# AMSTOMQTT.net
KiCad netlist of a schematic drawn in Altium Designer
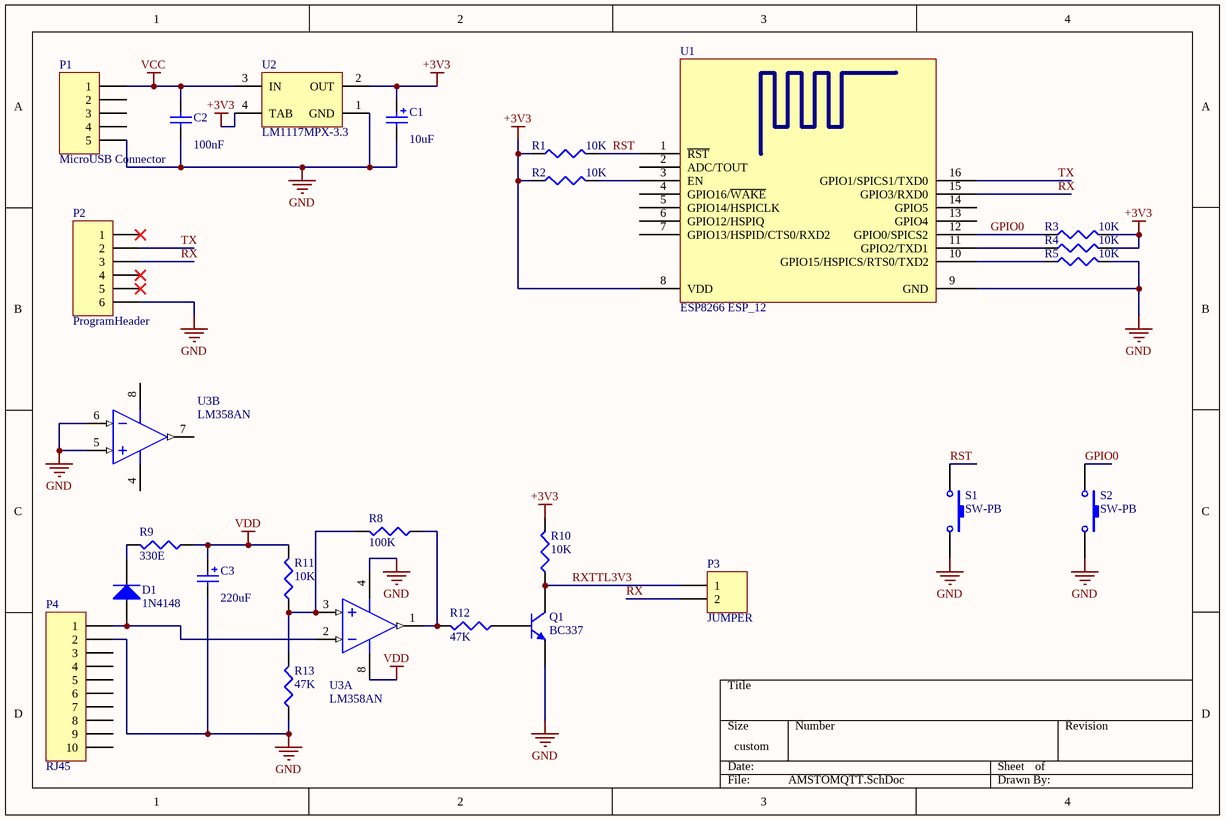
[diagram p0: AMSTOMQTT.SchDoc]

(export (version "E")
  (design (tool "Eeschema 10.0.6"))
  (components
    (comp (ref "C1")
      (value "10uF")
      (footprint "CAP(10uF/25V)")
      (description "Polarized Capacitor (Axial)")
      (fields (field (name "Comment") "Cap Pol2") (field (name "PUBLISHER") "Altium Limited"))
      (libsource (lib "Miscellaneous Devices") (part "Cap Pol2"))
    )
    (comp (ref "C2")
      (value "100nF")
      (footprint "RAD-0.2")
      (description "Capacitor")
      (fields (field (name "Comment") "Cap") (field (name "PUBLISHER") "Altium Limited"))
      (libsource (lib "Miscellaneous Devices") (part "Cap"))
    )
    (comp (ref "C3")
      (value "220uF")
      (footprint "CAP(10uF/25V)")
      (description "Polarized Capacitor (Axial)")
      (fields (field (name "Comment") "Cap Pol2") (field (name "PUBLISHER") "Altium Limited"))
      (libsource (lib "Miscellaneous Devices") (part "Cap Pol2"))
    )
    (comp (ref "D1")
      (value "1N4148")
      (footprint "DO-35")
      (description "High Conductance Fast Diode")
      (fields (field (name "PUBLISHER") "Altium Limited"))
      (libsource (lib "Miscellaneous Devices") (part "Diode 1N4148"))
    )
    (comp (ref "P1")
      (value "MicroUSB Connector")
      (footprint "MicroUSB")
      (description "Header, 5-Pin")
      (fields (field (name "PUBLISHER") "Altium Limited"))
      (libsource (lib "Miscellaneous Connectors") (part "Header 5"))
    )
    (comp (ref "P2")
      (value "ProgramHeader")
      (footprint "HDR1X6")
      (description "Header, 6-Pin")
      (fields (field (name "PUBLISHER") "Altium Limited"))
      (libsource (lib "Miscellaneous Connectors") (part "Header 6"))
    )
    (comp (ref "P3")
      (value "JUMPER")
      (footprint "HDR1X2")
      (description "Header, 2-Pin")
      (fields (field (name "PUBLISHER") "Altium Limited"))
      (libsource (lib "Miscellaneous Connectors") (part "Header 2"))
    )
    (comp (ref "P4")
      (value "RJ45")
      (footprint "RJ45")
      (description "Header, 10-Pin")
      (fields (field (name "PUBLISHER") "Altium Limited"))
      (libsource (lib "Miscellaneous Connectors") (part "Header 10"))
    )
    (comp (ref "Q1")
      (value "BC337")
      (footprint "TO-92")
      (description "NPN General Purpose Amplifier")
      (fields (field (name "PUBLISHER") "Altium Limited"))
      (libsource (lib "Miscellaneous Devices") (part "2N3904"))
    )
    (comp (ref "R1")
      (value "10K")
      (footprint "AXIAL-0.3")
      (description "Resistor")
      (fields (field (name "Comment") "Res3") (field (name "PUBLISHER") "Altium Limited"))
      (libsource (lib "Miscellaneous Devices") (part "Res3"))
    )
    (comp (ref "R2")
      (value "10K")
      (footprint "AXIAL-0.3")
      (description "Resistor")
      (fields (field (name "Comment") "Res3") (field (name "PUBLISHER") "Altium Limited"))
      (libsource (lib "Miscellaneous Devices") (part "Res3"))
    )
    (comp (ref "R3")
      (value "10K")
      (footprint "AXIAL-0.3")
      (description "Resistor")
      (fields (field (name "Comment") "Res3") (field (name "PUBLISHER") "Altium Limited"))
      (libsource (lib "Miscellaneous Devices") (part "Res3"))
    )
    (comp (ref "R4")
      (value "10K")
      (footprint "AXIAL-0.3")
      (description "Resistor")
      (fields (field (name "Comment") "Res3") (field (name "PUBLISHER") "Altium Limited"))
      (libsource (lib "Miscellaneous Devices") (part "Res3"))
    )
    (comp (ref "R5")
      (value "10K")
      (footprint "AXIAL-0.3")
      (description "Resistor")
      (fields (field (name "Comment") "Res3") (field (name "PUBLISHER") "Altium Limited"))
      (libsource (lib "Miscellaneous Devices") (part "Res3"))
    )
    (comp (ref "R8")
      (value "100K")
      (footprint "AXIAL-0.3")
      (description "Resistor")
      (fields (field (name "Comment") "Res3") (field (name "PUBLISHER") "Altium Limited"))
      (libsource (lib "Miscellaneous Devices") (part "Res3"))
    )
    (comp (ref "R9")
      (value "330E")
      (footprint "AXIAL-0.3")
      (description "Resistor")
      (fields (field (name "Comment") "Res3") (field (name "PUBLISHER") "Altium Limited"))
      (libsource (lib "Miscellaneous Devices") (part "Res3"))
    )
    (comp (ref "R10")
      (value "10K")
      (footprint "AXIAL-0.3")
      (description "Resistor")
      (fields (field (name "Comment") "Res3") (field (name "PUBLISHER") "Altium Limited"))
      (libsource (lib "Miscellaneous Devices") (part "Res3"))
    )
    (comp (ref "R11")
      (value "10K")
      (footprint "AXIAL-0.3")
      (description "Resistor")
      (fields (field (name "Comment") "Res3") (field (name "PUBLISHER") "Altium Limited"))
      (libsource (lib "Miscellaneous Devices") (part "Res3"))
    )
    (comp (ref "R12")
      (value "47K")
      (footprint "AXIAL-0.3")
      (description "Resistor")
      (fields (field (name "Comment") "Res3") (field (name "PUBLISHER") "Altium Limited"))
      (libsource (lib "Miscellaneous Devices") (part "Res3"))
    )
    (comp (ref "R13")
      (value "47K")
      (footprint "AXIAL-0.3")
      (description "Resistor")
      (fields (field (name "Comment") "Res3") (field (name "PUBLISHER") "Altium Limited"))
      (libsource (lib "Miscellaneous Devices") (part "Res3"))
    )
    (comp (ref "S1")
      (value "SW-PB")
      (footprint "PUSHBUTTON")
      (description "Switch")
      (fields (field (name "PUBLISHER") "Altium Limited"))
      (libsource (lib "Miscellaneous Devices") (part "SW-PB"))
    )
    (comp (ref "S2")
      (value "SW-PB")
      (footprint "PUSHBUTTON")
      (description "Switch")
      (fields (field (name "PUBLISHER") "Altium Limited"))
      (libsource (lib "Miscellaneous Devices") (part "SW-PB"))
    )
    (comp (ref "U1")
      (value "ESP8266 ESP_12")
      (footprint "ESP8266 ESP_12")
      (description "ESP8266 ESP-12")
      (fields (field (name "PUBLISHER") "Cynetik Group") (field (name "LATESTREVIEWER") "Zion Blue"))
      (libsource (lib "ESP8266") (part "ESP8266 ESP_12"))
    )
    (comp (ref "U2")
      (value "LM1117MPX-3.3")
      (footprint "MP04A_N")
      (description "800mA Low-Dropout Linear Regulator, 4-pin SOT-223")
      (fields (field (name "MANUFACTURER") "National Semiconductor"))
      (libsource (lib "National Semiconductor LDO") (part "LM1117MPX-3.3"))
    )
    (comp (ref "U3")
      (value "LM358AN")
      (footprint "N08E")
      (description "Low Power Dual Operational Amplifier, 8-pin MDIP")
      (fields (field (name "MANUFACTURER") "National Semiconductor"))
      (libsource (lib "National Semiconductor Amplifier") (part "LM358AN"))
    )
  )
  (nets
    (net (code "1") (name "+3V3") (class "Default")
      (node (ref "C1") (pin "1") (pinfunction "1_1") (pintype "passive"))
      (node (ref "R1") (pin "1") (pinfunction "1_1") (pintype "passive"))
      (node (ref "R10") (pin "2") (pinfunction "2_2") (pintype "passive"))
      (node (ref "R2") (pin "1") (pinfunction "1_1") (pintype "passive"))
      (node (ref "R3") (pin "2") (pinfunction "2_2") (pintype "passive"))
      (node (ref "R4") (pin "2") (pinfunction "2_2") (pintype "passive"))
      (node (ref "U1") (pin "8") (pinfunction "VDD_8") (pintype "passive"))
      (node (ref "U2") (pin "2") (pinfunction "OUT_2") (pintype "power_in"))
      (node (ref "U2") (pin "4") (pinfunction "TAB_4") (pintype "power_in"))
    )
    (net (code "2") (name "/GPIO0") (class "Default")
      (node (ref "R3") (pin "1") (pinfunction "1_1") (pintype "passive"))
      (node (ref "S2") (pin "1") (pinfunction "1_1") (pintype "passive"))
      (node (ref "U1") (pin "12") (pinfunction "GPIO0/SPICS2_12") (pintype "passive"))
    )
    (net (code "3") (name "/RST") (class "Default")
      (node (ref "R1") (pin "2") (pinfunction "2_2") (pintype "passive"))
      (node (ref "S1") (pin "1") (pinfunction "1_1") (pintype "passive"))
      (node (ref "U1") (pin "1") (pinfunction "~{RST}_1") (pintype "passive"))
    )
    (net (code "4") (name "/RX") (class "Default")
      (node (ref "P2") (pin "3") (pinfunction "3_3") (pintype "passive"))
      (node (ref "P3") (pin "2") (pinfunction "2_2") (pintype "passive"))
      (node (ref "U1") (pin "15") (pinfunction "GPIO3/RXD0_15") (pintype "passive"))
    )
    (net (code "5") (name "/RXTTL3V3") (class "Default")
      (node (ref "P3") (pin "1") (pinfunction "1_1") (pintype "passive"))
      (node (ref "Q1") (pin "3") (pinfunction "C_3") (pintype "passive"))
      (node (ref "R10") (pin "1") (pinfunction "1_1") (pintype "passive"))
    )
    (net (code "6") (name "/TX") (class "Default")
      (node (ref "P2") (pin "2") (pinfunction "2_2") (pintype "passive"))
      (node (ref "U1") (pin "16") (pinfunction "GPIO1/SPICS1/TXD0_16") (pintype "passive"))
    )
    (net (code "7") (name "GND") (class "Default")
      (node (ref "C1") (pin "2") (pinfunction "2_2") (pintype "passive"))
      (node (ref "C2") (pin "1") (pinfunction "1_1") (pintype "passive"))
      (node (ref "C3") (pin "2") (pinfunction "2_2") (pintype "passive"))
      (node (ref "P1") (pin "5") (pinfunction "5_5") (pintype "passive"))
      (node (ref "P2") (pin "6") (pinfunction "6_6") (pintype "passive"))
      (node (ref "P4") (pin "2") (pinfunction "2_2") (pintype "passive"))
      (node (ref "Q1") (pin "1") (pinfunction "E_1") (pintype "passive"))
      (node (ref "R13") (pin "1") (pinfunction "1_1") (pintype "passive"))
      (node (ref "R5") (pin "2") (pinfunction "2_2") (pintype "passive"))
      (node (ref "S1") (pin "2") (pinfunction "2_2") (pintype "passive"))
      (node (ref "S2") (pin "2") (pinfunction "2_2") (pintype "passive"))
      (node (ref "U1") (pin "9") (pinfunction "GND_9") (pintype "passive"))
      (node (ref "U2") (pin "1") (pinfunction "GND_1") (pintype "power_in"))
      (node (ref "U3") (pin "4") (pinfunction "GND_4") (pintype "power_in"))
      (node (ref "U3") (pin "5") (pinfunction "INB+_5") (pintype "input"))
      (node (ref "U3") (pin "6") (pinfunction "INB-_6") (pintype "input"))
    )
    (net (code "8") (name "Net-(D1-A)") (class "Default")
      (node (ref "D1") (pin "1") (pinfunction "A_1") (pintype "passive"))
      (node (ref "P4") (pin "1") (pinfunction "1_1") (pintype "passive"))
      (node (ref "U3") (pin "2") (pinfunction "INA-_2") (pintype "input"))
    )
    (net (code "9") (name "Net-(D1-K)") (class "Default")
      (node (ref "D1") (pin "2") (pinfunction "K_2") (pintype "passive"))
      (node (ref "R9") (pin "2") (pinfunction "2_2") (pintype "passive"))
    )
    (net (code "10") (name "Net-(Q1-B)") (class "Default")
      (node (ref "Q1") (pin "2") (pinfunction "B_2") (pintype "passive"))
      (node (ref "R12") (pin "1") (pinfunction "1_1") (pintype "passive"))
    )
    (net (code "11") (name "Net-(U1-EN)") (class "Default")
      (node (ref "R2") (pin "2") (pinfunction "2_2") (pintype "passive"))
      (node (ref "U1") (pin "3") (pinfunction "EN_3") (pintype "passive"))
    )
    (net (code "12") (name "Net-(U1-GPIO2{slash}TXD1)") (class "Default")
      (node (ref "R4") (pin "1") (pinfunction "1_1") (pintype "passive"))
      (node (ref "U1") (pin "11") (pinfunction "GPIO2/TXD1_11") (pintype "passive"))
    )
    (net (code "13") (name "Net-(U1-GPIO15{slash}HSPICS{slash}RTS0{slash}TXD2)") (class "Default")
      (node (ref "R5") (pin "1") (pinfunction "1_1") (pintype "passive"))
      (node (ref "U1") (pin "10") (pinfunction "GPIO15/HSPICS/RTS0/TXD2_10") (pintype "passive"))
    )
    (net (code "14") (name "Net-(U3A-INA+)") (class "Default")
      (node (ref "R11") (pin "1") (pinfunction "1_1") (pintype "passive"))
      (node (ref "R13") (pin "2") (pinfunction "2_2") (pintype "passive"))
      (node (ref "R8") (pin "2") (pinfunction "2_2") (pintype "passive"))
      (node (ref "U3") (pin "3") (pinfunction "INA+_3") (pintype "input"))
    )
    (net (code "15") (name "Net-(U3A-OUTA)") (class "Default")
      (node (ref "R12") (pin "2") (pinfunction "2_2") (pintype "passive"))
      (node (ref "R8") (pin "1") (pinfunction "1_1") (pintype "passive"))
      (node (ref "U3") (pin "1") (pinfunction "OUTA_1") (pintype "output"))
    )
    (net (code "16") (name "VCC") (class "Default")
      (node (ref "C2") (pin "2") (pinfunction "2_2") (pintype "passive"))
      (node (ref "P1") (pin "1") (pinfunction "1_1") (pintype "passive"))
      (node (ref "U2") (pin "3") (pinfunction "IN_3") (pintype "power_in"))
    )
    (net (code "17") (name "VDD") (class "Default")
      (node (ref "C3") (pin "1") (pinfunction "1_1") (pintype "passive"))
      (node (ref "R11") (pin "2") (pinfunction "2_2") (pintype "passive"))
      (node (ref "R9") (pin "1") (pinfunction "1_1") (pintype "passive"))
      (node (ref "U3") (pin "8") (pinfunction "V+_8") (pintype "power_in"))
    )
    (net (code "18") (name "unconnected-(P1-Pad2)") (class "Default")
      (node (ref "P1") (pin "2") (pinfunction "2_2") (pintype "passive"))
    )
    (net (code "19") (name "unconnected-(P1-Pad3)") (class "Default")
      (node (ref "P1") (pin "3") (pinfunction "3_3") (pintype "passive"))
    )
    (net (code "20") (name "unconnected-(P1-Pad4)") (class "Default")
      (node (ref "P1") (pin "4") (pinfunction "4_4") (pintype "passive"))
    )
    (net (code "21") (name "unconnected-(P2-Pad1)") (class "Default")
      (node (ref "P2") (pin "1") (pinfunction "1_1") (pintype "passive+no_connect"))
    )
    (net (code "22") (name "unconnected-(P2-Pad4)") (class "Default")
      (node (ref "P2") (pin "4") (pinfunction "4_4") (pintype "passive+no_connect"))
    )
    (net (code "23") (name "unconnected-(P2-Pad5)") (class "Default")
      (node (ref "P2") (pin "5") (pinfunction "5_5") (pintype "passive+no_connect"))
    )
    (net (code "24") (name "unconnected-(P4-Pad3)") (class "Default")
      (node (ref "P4") (pin "3") (pinfunction "3_3") (pintype "passive"))
    )
    (net (code "25") (name "unconnected-(P4-Pad4)") (class "Default")
      (node (ref "P4") (pin "4") (pinfunction "4_4") (pintype "passive"))
    )
    (net (code "26") (name "unconnected-(P4-Pad5)") (class "Default")
      (node (ref "P4") (pin "5") (pinfunction "5_5") (pintype "passive"))
    )
    (net (code "27") (name "unconnected-(P4-Pad6)") (class "Default")
      (node (ref "P4") (pin "6") (pinfunction "6_6") (pintype "passive"))
    )
    (net (code "28") (name "unconnected-(P4-Pad7)") (class "Default")
      (node (ref "P4") (pin "7") (pinfunction "7_7") (pintype "passive"))
    )
    (net (code "29") (name "unconnected-(P4-Pad8)") (class "Default")
      (node (ref "P4") (pin "8") (pinfunction "8_8") (pintype "passive"))
    )
    (net (code "30") (name "unconnected-(P4-Pad9)") (class "Default")
      (node (ref "P4") (pin "9") (pinfunction "9_9") (pintype "passive"))
    )
    (net (code "31") (name "unconnected-(P4-Pad10)") (class "Default")
      (node (ref "P4") (pin "10") (pinfunction "10_10") (pintype "passive"))
    )
    (net (code "32") (name "unconnected-(U1-ADC{slash}TOUT-Pad2)") (class "Default")
      (node (ref "U1") (pin "2") (pinfunction "ADC/TOUT_2") (pintype "passive"))
    )
    (net (code "33") (name "unconnected-(U1-GPIO4-Pad13)") (class "Default")
      (node (ref "U1") (pin "13") (pinfunction "GPIO4_13") (pintype "passive"))
    )
    (net (code "34") (name "unconnected-(U1-GPIO5-Pad14)") (class "Default")
      (node (ref "U1") (pin "14") (pinfunction "GPIO5_14") (pintype "passive"))
    )
    (net (code "35") (name "unconnected-(U1-GPIO12{slash}HSPIQ-Pad6)") (class "Default")
      (node (ref "U1") (pin "6") (pinfunction "GPIO12/HSPIQ_6") (pintype "passive"))
    )
    (net (code "36") (name "unconnected-(U1-GPIO13{slash}HSPID{slash}CTS0{slash}RXD2-Pad7)") (class "Default")
      (node (ref "U1") (pin "7") (pinfunction "GPIO13/HSPID/CTS0/RXD2_7") (pintype "passive"))
    )
    (net (code "37") (name "unconnected-(U1-GPIO14{slash}HSPICLK-Pad5)") (class "Default")
      (node (ref "U1") (pin "5") (pinfunction "GPIO14/HSPICLK_5") (pintype "passive"))
    )
    (net (code "38") (name "unconnected-(U1-GPIO16{slash}~{WAKE}-Pad4)") (class "Default")
      (node (ref "U1") (pin "4") (pinfunction "GPIO16/~{WAKE}_4") (pintype "passive"))
    )
    (net (code "39") (name "unconnected-(U3B-GND-Pad4)") (class "Default")
      (node (ref "U3") (pin "4") (pinfunction "GND_4") (pintype "power_in"))
    )
    (net (code "40") (name "unconnected-(U3B-OUTB-Pad7)") (class "Default")
      (node (ref "U3") (pin "7") (pinfunction "OUTB_7") (pintype "output"))
    )
    (net (code "41") (name "unconnected-(U3B-V+-Pad8)") (class "Default")
      (node (ref "U3") (pin "8") (pinfunction "V+_8") (pintype "power_in"))
    )
  )
)
